# Thermostat.net
KiCad netlist of a schematic drawn in EAGLE
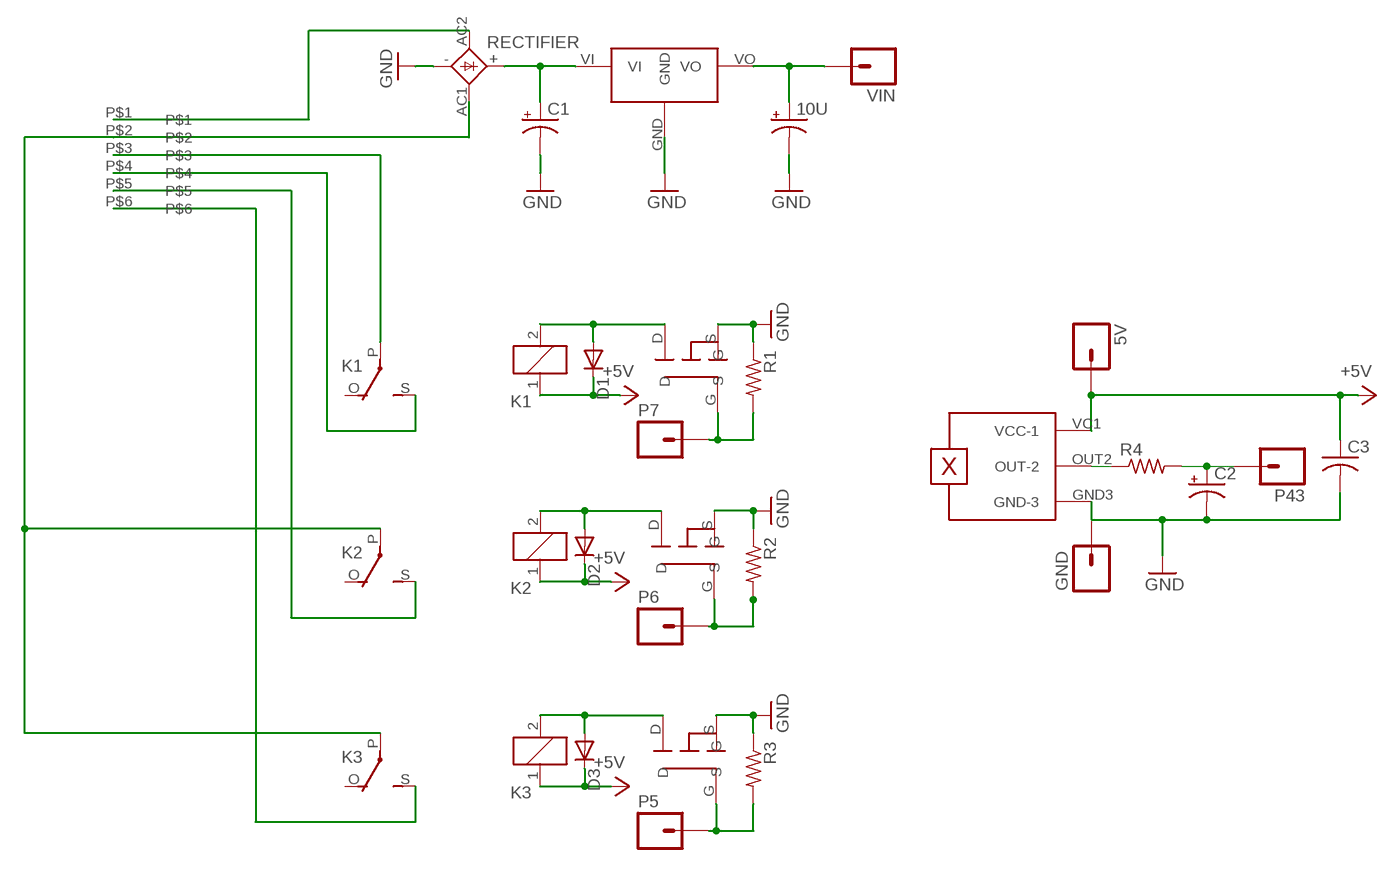
[diagram p0: schematic, sheet 1]

(export (version "E")
  (design (tool "Eeschema 10.0.6"))
  (components
    (comp (ref "5V")
      (value "M01PTH")
      (footprint "eagle-import:1X01")
      (libsource (lib "eagle-import") (part "M01PTH"))
    )
    (comp (ref "10U")
      (value "CAP_POLPTH2")
      (footprint "eagle-import:CPOL-RADIAL-10UF-25V")
      (libsource (lib "eagle-import") (part "CAP_POLPTH2"))
    )
    (comp (ref "C1")
      (value "CPOL-USE5-10.5")
      (footprint "eagle-import:E5-10,5")
      (libsource (lib "eagle-import") (part "CPOL-USE5-10.5"))
    )
    (comp (ref "C2")
      (value "CPOL-USE2-5")
      (footprint "eagle-import:E2-5")
      (libsource (lib "eagle-import") (part "CPOL-USE2-5"))
    )
    (comp (ref "C3")
      (value "C-US050-024X044")
      (footprint "eagle-import:C050-024X044")
      (libsource (lib "eagle-import") (part "C-US050-024X044"))
    )
    (comp (ref "D1")
      (value "1N4446")
      (footprint "eagle-import:DO35-10")
      (libsource (lib "eagle-import") (part "1N4446"))
    )
    (comp (ref "D2")
      (value "1N4446")
      (footprint "eagle-import:DO35-10")
      (libsource (lib "eagle-import") (part "1N4446"))
    )
    (comp (ref "D3")
      (value "1N4446")
      (footprint "eagle-import:DO35-10")
      (libsource (lib "eagle-import") (part "1N4446"))
    )
    (comp (ref "GND")
      (value "M01PTH")
      (footprint "eagle-import:1X01")
      (libsource (lib "eagle-import") (part "M01PTH"))
    )
    (comp (ref "K1")
      (value "G5LE")
      (footprint "eagle-import:G5LE")
      (libsource (lib "eagle-import") (part "G5LE"))
    )
    (comp (ref "K2")
      (value "G5LE")
      (footprint "eagle-import:G5LE")
      (libsource (lib "eagle-import") (part "G5LE"))
    )
    (comp (ref "K3")
      (value "G5LE")
      (footprint "eagle-import:G5LE")
      (libsource (lib "eagle-import") (part "G5LE"))
    )
    (comp (ref "P5")
      (value "M01PTH")
      (footprint "eagle-import:1X01")
      (libsource (lib "eagle-import") (part "M01PTH"))
    )
    (comp (ref "P6")
      (value "M01PTH")
      (footprint "eagle-import:1X01")
      (libsource (lib "eagle-import") (part "M01PTH"))
    )
    (comp (ref "P7")
      (value "M01PTH")
      (footprint "eagle-import:1X01")
      (libsource (lib "eagle-import") (part "M01PTH"))
    )
    (comp (ref "P43")
      (value "M01PTH")
      (footprint "eagle-import:1X01")
      (libsource (lib "eagle-import") (part "M01PTH"))
    )
    (comp (ref "R1")
      (value "R-US_0204/7")
      (footprint "eagle-import:0204_7")
      (libsource (lib "eagle-import") (part "R-US_0204/7"))
    )
    (comp (ref "R2")
      (value "R-US_0204/7")
      (footprint "eagle-import:0204_7")
      (libsource (lib "eagle-import") (part "R-US_0204/7"))
    )
    (comp (ref "R3")
      (value "R-US_0204/7")
      (footprint "eagle-import:0204_7")
      (libsource (lib "eagle-import") (part "R-US_0204/7"))
    )
    (comp (ref "R4")
      (value "R-US_0204/7")
      (footprint "eagle-import:0204_7")
      (libsource (lib "eagle-import") (part "R-US_0204/7"))
    )
    (comp (ref "RECTIFIER")
      (value "GBU4")
      (footprint "eagle-import:GBU4S")
      (libsource (lib "eagle-import") (part "GBU4"))
    )
    (comp (ref "U$1")
      (value "TMP36")
      (footprint "eagle-import:TMP36")
      (libsource (lib "eagle-import") (part "TMP36"))
    )
    (comp (ref "U$2")
      (value "V715W-500R")
      (footprint "eagle-import:SWITCHINGREGULATOR")
      (libsource (lib "eagle-import") (part "V715W-500R"))
    )
    (comp (ref "U$3")
      (value "PHOENIX-651-1935200")
      (footprint "eagle-import:PHOENIX_E_5MM_6PIN")
      (libsource (lib "eagle-import") (part "PHOENIX-651-1935200"))
    )
    (comp (ref "U$4")
      (value "TRANSISTOR")
      (footprint "eagle-import:TRANSISTOR")
      (libsource (lib "eagle-import") (part "TRANSISTOR"))
    )
    (comp (ref "U$5")
      (value "TRANSISTOR")
      (footprint "eagle-import:TRANSISTOR")
      (libsource (lib "eagle-import") (part "TRANSISTOR"))
    )
    (comp (ref "U$6")
      (value "TRANSISTOR")
      (footprint "eagle-import:TRANSISTOR")
      (libsource (lib "eagle-import") (part "TRANSISTOR"))
    )
    (comp (ref "VIN")
      (value "M01PTH")
      (footprint "eagle-import:1X01")
      (libsource (lib "eagle-import") (part "M01PTH"))
    )
  )
  (nets
    (net (code "1") (name "+5V") (class "Default")
      (node (ref "5V") (pin "1") (pinfunction "1_1") (pintype "passive"))
      (node (ref "C3") (pin "1") (pinfunction "1_1") (pintype "passive"))
      (node (ref "D1") (pin "C") (pinfunction "C_C") (pintype "passive"))
      (node (ref "D2") (pin "C") (pinfunction "C_C") (pintype "passive"))
      (node (ref "D3") (pin "C") (pinfunction "C_C") (pintype "passive"))
      (node (ref "K1") (pin "1") (pinfunction "1_1") (pintype "passive"))
      (node (ref "K2") (pin "1") (pinfunction "1_1") (pintype "passive"))
      (node (ref "K3") (pin "1") (pinfunction "1_1") (pintype "passive"))
      (node (ref "U$1") (pin "VC1") (pinfunction "VCC-1_VC1") (pintype "bidirectional"))
    )
    (net (code "2") (name "GND") (class "Default")
      (node (ref "10U") (pin "2") (pinfunction "-_2") (pintype "passive"))
      (node (ref "C1") (pin "-") (pinfunction "-_-") (pintype "passive"))
      (node (ref "C2") (pin "-") (pinfunction "-_-") (pintype "passive"))
      (node (ref "C3") (pin "2") (pinfunction "2_2") (pintype "passive"))
      (node (ref "GND") (pin "1") (pinfunction "1_1") (pintype "passive"))
      (node (ref "R1") (pin "1") (pinfunction "1_1") (pintype "passive"))
      (node (ref "R2") (pin "1") (pinfunction "1_1") (pintype "passive"))
      (node (ref "R3") (pin "1") (pinfunction "1_1") (pintype "passive"))
      (node (ref "RECTIFIER") (pin "-") (pinfunction "-_-") (pintype "passive"))
      (node (ref "U$1") (pin "GND3") (pinfunction "GND-3_GND3") (pintype "bidirectional"))
      (node (ref "U$2") (pin "GND") (pinfunction "GND_GND") (pintype "bidirectional"))
      (node (ref "U$4") (pin "S") (pinfunction "S_S") (pintype "bidirectional"))
      (node (ref "U$5") (pin "S") (pinfunction "S_S") (pintype "bidirectional"))
      (node (ref "U$6") (pin "S") (pinfunction "S_S") (pintype "bidirectional"))
    )
    (net (code "3") (name "Net-(10U-+)") (class "Default")
      (node (ref "10U") (pin "1") (pinfunction "+_1") (pintype "passive"))
      (node (ref "U$2") (pin "VO") (pinfunction "VO_VO") (pintype "bidirectional"))
      (node (ref "VIN") (pin "1") (pinfunction "1_1") (pintype "passive"))
    )
    (net (code "4") (name "Net-(C1-Pad+)") (class "Default")
      (node (ref "C1") (pin "+") (pinfunction "+_+") (pintype "passive"))
      (node (ref "RECTIFIER") (pin "+") (pinfunction "+_+") (pintype "passive"))
      (node (ref "U$2") (pin "VI") (pinfunction "VI_VI") (pintype "bidirectional"))
    )
    (net (code "5") (name "Net-(C2-Pad+)") (class "Default")
      (node (ref "C2") (pin "+") (pinfunction "+_+") (pintype "passive"))
      (node (ref "P43") (pin "1") (pinfunction "1_1") (pintype "passive"))
      (node (ref "R4") (pin "2") (pinfunction "2_2") (pintype "passive"))
    )
    (net (code "6") (name "Net-(D1-PadA)") (class "Default")
      (node (ref "D1") (pin "A") (pinfunction "A_A") (pintype "passive"))
      (node (ref "K1") (pin "2") (pinfunction "2_2") (pintype "passive"))
      (node (ref "U$6") (pin "D") (pinfunction "D_D") (pintype "bidirectional"))
    )
    (net (code "7") (name "Net-(D2-PadA)") (class "Default")
      (node (ref "D2") (pin "A") (pinfunction "A_A") (pintype "passive"))
      (node (ref "K2") (pin "2") (pinfunction "2_2") (pintype "passive"))
      (node (ref "U$5") (pin "D") (pinfunction "D_D") (pintype "bidirectional"))
    )
    (net (code "8") (name "Net-(D3-PadA)") (class "Default")
      (node (ref "D3") (pin "A") (pinfunction "A_A") (pintype "passive"))
      (node (ref "K3") (pin "2") (pinfunction "2_2") (pintype "passive"))
      (node (ref "U$4") (pin "D") (pinfunction "D_D") (pintype "bidirectional"))
    )
    (net (code "9") (name "Net-(K1-PadP)") (class "Default")
      (node (ref "K1") (pin "P") (pinfunction "P_P") (pintype "passive"))
      (node (ref "U$3") (pin "P$3") (pinfunction "P$3_P$3") (pintype "bidirectional"))
    )
    (net (code "10") (name "Net-(K1-PadS)") (class "Default")
      (node (ref "K1") (pin "S") (pinfunction "S_S") (pintype "passive"))
      (node (ref "U$3") (pin "P$4") (pinfunction "P$4_P$4") (pintype "bidirectional"))
    )
    (net (code "11") (name "Net-(K2-PadS)") (class "Default")
      (node (ref "K2") (pin "S") (pinfunction "S_S") (pintype "passive"))
      (node (ref "U$3") (pin "P$5") (pinfunction "P$5_P$5") (pintype "bidirectional"))
    )
    (net (code "12") (name "Net-(K3-PadS)") (class "Default")
      (node (ref "K3") (pin "S") (pinfunction "S_S") (pintype "passive"))
      (node (ref "U$3") (pin "P$6") (pinfunction "P$6_P$6") (pintype "bidirectional"))
    )
    (net (code "13") (name "Net-(P5-Pad1)") (class "Default")
      (node (ref "P5") (pin "1") (pinfunction "1_1") (pintype "passive"))
      (node (ref "R3") (pin "2") (pinfunction "2_2") (pintype "passive"))
      (node (ref "U$4") (pin "G") (pinfunction "G_G") (pintype "bidirectional"))
    )
    (net (code "14") (name "Net-(P6-Pad1)") (class "Default")
      (node (ref "P6") (pin "1") (pinfunction "1_1") (pintype "passive"))
      (node (ref "R2") (pin "2") (pinfunction "2_2") (pintype "passive"))
      (node (ref "U$5") (pin "G") (pinfunction "G_G") (pintype "bidirectional"))
    )
    (net (code "15") (name "Net-(P7-Pad1)") (class "Default")
      (node (ref "P7") (pin "1") (pinfunction "1_1") (pintype "passive"))
      (node (ref "R1") (pin "2") (pinfunction "2_2") (pintype "passive"))
      (node (ref "U$6") (pin "G") (pinfunction "G_G") (pintype "bidirectional"))
    )
    (net (code "16") (name "Net-(RECTIFIER-AC1)") (class "Default")
      (node (ref "RECTIFIER") (pin "AC2") (pinfunction "AC1_AC2") (pintype "passive"))
      (node (ref "U$3") (pin "P$1") (pinfunction "P$1_P$1") (pintype "bidirectional"))
    )
    (net (code "17") (name "Net-(RECTIFIER-AC2)") (class "Default")
      (node (ref "K2") (pin "P") (pinfunction "P_P") (pintype "passive"))
      (node (ref "K3") (pin "P") (pinfunction "P_P") (pintype "passive"))
      (node (ref "RECTIFIER") (pin "AC1") (pinfunction "AC2_AC1") (pintype "passive"))
      (node (ref "U$3") (pin "P$2") (pinfunction "P$2_P$2") (pintype "bidirectional"))
    )
    (net (code "18") (name "Net-(U$1-OUT-2)") (class "Default")
      (node (ref "R4") (pin "1") (pinfunction "1_1") (pintype "passive"))
      (node (ref "U$1") (pin "OUT2") (pinfunction "OUT-2_OUT2") (pintype "bidirectional"))
    )
    (net (code "19") (name "unconnected-(K1-PadO)") (class "Default")
      (node (ref "K1") (pin "O") (pinfunction "O_O") (pintype "passive"))
    )
    (net (code "20") (name "unconnected-(K2-PadO)") (class "Default")
      (node (ref "K2") (pin "O") (pinfunction "O_O") (pintype "passive"))
    )
    (net (code "21") (name "unconnected-(K3-PadO)") (class "Default")
      (node (ref "K3") (pin "O") (pinfunction "O_O") (pintype "passive"))
    )
  )
)
